# head_board.net
KiCad netlist of a schematic drawn in EAGLE
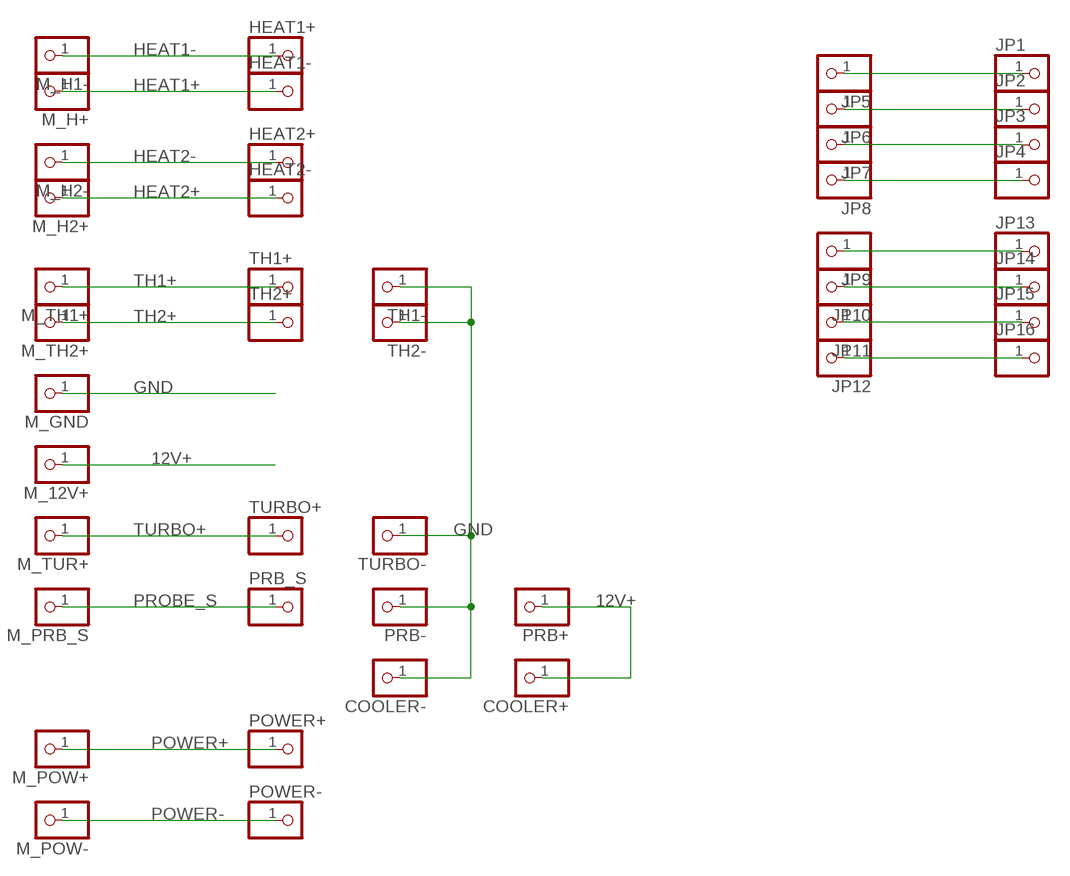
[diagram p0: schematic, sheet 1]

(export (version "E")
  (design (tool "Eeschema 10.0.6"))
  (components
    (comp (ref "COOLER+")
      (value "PINHD-1X1")
      (footprint "eagle-import:1X01")
      (libsource (lib "eagle-import") (part "PINHD-1X1"))
    )
    (comp (ref "COOLER-")
      (value "PINHD-1X1")
      (footprint "eagle-import:1X01")
      (libsource (lib "eagle-import") (part "PINHD-1X1"))
    )
    (comp (ref "HEAT1+")
      (value "PINHD-1X1")
      (footprint "eagle-import:1X01")
      (libsource (lib "eagle-import") (part "PINHD-1X1"))
    )
    (comp (ref "HEAT1-")
      (value "PINHD-1X1")
      (footprint "eagle-import:1X01")
      (libsource (lib "eagle-import") (part "PINHD-1X1"))
    )
    (comp (ref "HEAT2+")
      (value "PINHD-1X1")
      (footprint "eagle-import:1X01")
      (libsource (lib "eagle-import") (part "PINHD-1X1"))
    )
    (comp (ref "HEAT2-")
      (value "PINHD-1X1")
      (footprint "eagle-import:1X01")
      (libsource (lib "eagle-import") (part "PINHD-1X1"))
    )
    (comp (ref "JP1")
      (value "PINHD-1X1")
      (footprint "eagle-import:1X01")
      (libsource (lib "eagle-import") (part "PINHD-1X1"))
    )
    (comp (ref "JP2")
      (value "PINHD-1X1")
      (footprint "eagle-import:1X01")
      (libsource (lib "eagle-import") (part "PINHD-1X1"))
    )
    (comp (ref "JP3")
      (value "PINHD-1X1")
      (footprint "eagle-import:1X01")
      (libsource (lib "eagle-import") (part "PINHD-1X1"))
    )
    (comp (ref "JP4")
      (value "PINHD-1X1")
      (footprint "eagle-import:1X01")
      (libsource (lib "eagle-import") (part "PINHD-1X1"))
    )
    (comp (ref "JP5")
      (value "PINHD-1X1")
      (footprint "eagle-import:1X01")
      (libsource (lib "eagle-import") (part "PINHD-1X1"))
    )
    (comp (ref "JP6")
      (value "PINHD-1X1")
      (footprint "eagle-import:1X01")
      (libsource (lib "eagle-import") (part "PINHD-1X1"))
    )
    (comp (ref "JP7")
      (value "PINHD-1X1")
      (footprint "eagle-import:1X01")
      (libsource (lib "eagle-import") (part "PINHD-1X1"))
    )
    (comp (ref "JP8")
      (value "PINHD-1X1")
      (footprint "eagle-import:1X01")
      (libsource (lib "eagle-import") (part "PINHD-1X1"))
    )
    (comp (ref "JP9")
      (value "PINHD-1X1")
      (footprint "eagle-import:1X01")
      (libsource (lib "eagle-import") (part "PINHD-1X1"))
    )
    (comp (ref "JP10")
      (value "PINHD-1X1")
      (footprint "eagle-import:1X01")
      (libsource (lib "eagle-import") (part "PINHD-1X1"))
    )
    (comp (ref "JP11")
      (value "PINHD-1X1")
      (footprint "eagle-import:1X01")
      (libsource (lib "eagle-import") (part "PINHD-1X1"))
    )
    (comp (ref "JP12")
      (value "PINHD-1X1")
      (footprint "eagle-import:1X01")
      (libsource (lib "eagle-import") (part "PINHD-1X1"))
    )
    (comp (ref "JP13")
      (value "PINHD-1X1")
      (footprint "eagle-import:1X01")
      (libsource (lib "eagle-import") (part "PINHD-1X1"))
    )
    (comp (ref "JP14")
      (value "PINHD-1X1")
      (footprint "eagle-import:1X01")
      (libsource (lib "eagle-import") (part "PINHD-1X1"))
    )
    (comp (ref "JP15")
      (value "PINHD-1X1")
      (footprint "eagle-import:1X01")
      (libsource (lib "eagle-import") (part "PINHD-1X1"))
    )
    (comp (ref "JP16")
      (value "PINHD-1X1")
      (footprint "eagle-import:1X01")
      (libsource (lib "eagle-import") (part "PINHD-1X1"))
    )
    (comp (ref "M_12V+")
      (value "PINHD-1X1")
      (footprint "eagle-import:1X01")
      (libsource (lib "eagle-import") (part "PINHD-1X1"))
    )
    (comp (ref "M_GND")
      (value "PINHD-1X1")
      (footprint "eagle-import:1X01")
      (libsource (lib "eagle-import") (part "PINHD-1X1"))
    )
    (comp (ref "M_H+")
      (value "PINHD-1X1")
      (footprint "eagle-import:1X01")
      (libsource (lib "eagle-import") (part "PINHD-1X1"))
    )
    (comp (ref "M_H1-")
      (value "PINHD-1X1")
      (footprint "eagle-import:1X01")
      (libsource (lib "eagle-import") (part "PINHD-1X1"))
    )
    (comp (ref "M_H2+")
      (value "PINHD-1X1")
      (footprint "eagle-import:1X01")
      (libsource (lib "eagle-import") (part "PINHD-1X1"))
    )
    (comp (ref "M_H2-")
      (value "PINHD-1X1")
      (footprint "eagle-import:1X01")
      (libsource (lib "eagle-import") (part "PINHD-1X1"))
    )
    (comp (ref "M_POW+")
      (value "PINHD-1X1")
      (footprint "eagle-import:1X01")
      (libsource (lib "eagle-import") (part "PINHD-1X1"))
    )
    (comp (ref "M_POW-")
      (value "PINHD-1X1")
      (footprint "eagle-import:1X01")
      (libsource (lib "eagle-import") (part "PINHD-1X1"))
    )
    (comp (ref "M_PRB_S")
      (value "PINHD-1X1")
      (footprint "eagle-import:1X01")
      (libsource (lib "eagle-import") (part "PINHD-1X1"))
    )
    (comp (ref "M_TH1+")
      (value "PINHD-1X1")
      (footprint "eagle-import:1X01")
      (libsource (lib "eagle-import") (part "PINHD-1X1"))
    )
    (comp (ref "M_TH2+")
      (value "PINHD-1X1")
      (footprint "eagle-import:1X01")
      (libsource (lib "eagle-import") (part "PINHD-1X1"))
    )
    (comp (ref "M_TUR+")
      (value "PINHD-1X1")
      (footprint "eagle-import:1X01")
      (libsource (lib "eagle-import") (part "PINHD-1X1"))
    )
    (comp (ref "POWER+")
      (value "PINHD-1X1")
      (footprint "eagle-import:1X01")
      (libsource (lib "eagle-import") (part "PINHD-1X1"))
    )
    (comp (ref "POWER-")
      (value "PINHD-1X1")
      (footprint "eagle-import:1X01")
      (libsource (lib "eagle-import") (part "PINHD-1X1"))
    )
    (comp (ref "PRB+")
      (value "PINHD-1X1")
      (footprint "eagle-import:1X01")
      (libsource (lib "eagle-import") (part "PINHD-1X1"))
    )
    (comp (ref "PRB-")
      (value "PINHD-1X1")
      (footprint "eagle-import:1X01")
      (libsource (lib "eagle-import") (part "PINHD-1X1"))
    )
    (comp (ref "PRB_S")
      (value "PINHD-1X1")
      (footprint "eagle-import:1X01")
      (libsource (lib "eagle-import") (part "PINHD-1X1"))
    )
    (comp (ref "TH1+")
      (value "PINHD-1X1")
      (footprint "eagle-import:1X01")
      (libsource (lib "eagle-import") (part "PINHD-1X1"))
    )
    (comp (ref "TH1-")
      (value "PINHD-1X1")
      (footprint "eagle-import:1X01")
      (libsource (lib "eagle-import") (part "PINHD-1X1"))
    )
    (comp (ref "TH2+")
      (value "PINHD-1X1")
      (footprint "eagle-import:1X01")
      (libsource (lib "eagle-import") (part "PINHD-1X1"))
    )
    (comp (ref "TH2-")
      (value "PINHD-1X1")
      (footprint "eagle-import:1X01")
      (libsource (lib "eagle-import") (part "PINHD-1X1"))
    )
    (comp (ref "TURBO+")
      (value "PINHD-1X1")
      (footprint "eagle-import:1X01")
      (libsource (lib "eagle-import") (part "PINHD-1X1"))
    )
    (comp (ref "TURBO-")
      (value "PINHD-1X1")
      (footprint "eagle-import:1X01")
      (libsource (lib "eagle-import") (part "PINHD-1X1"))
    )
  )
  (nets
    (net (code "1") (name "/12V+") (class "Default")
      (node (ref "COOLER+") (pin "1") (pinfunction "1_1") (pintype "passive"))
      (node (ref "M_12V+") (pin "1") (pinfunction "1_1") (pintype "passive"))
      (node (ref "PRB+") (pin "1") (pinfunction "1_1") (pintype "passive"))
    )
    (net (code "2") (name "/GND") (class "Default")
      (node (ref "COOLER-") (pin "1") (pinfunction "1_1") (pintype "passive"))
      (node (ref "M_GND") (pin "1") (pinfunction "1_1") (pintype "passive"))
      (node (ref "PRB-") (pin "1") (pinfunction "1_1") (pintype "passive"))
      (node (ref "TH1-") (pin "1") (pinfunction "1_1") (pintype "passive"))
      (node (ref "TH2-") (pin "1") (pinfunction "1_1") (pintype "passive"))
      (node (ref "TURBO-") (pin "1") (pinfunction "1_1") (pintype "passive"))
    )
    (net (code "3") (name "/HEAT1+") (class "Default")
      (node (ref "HEAT1-") (pin "1") (pinfunction "1_1") (pintype "passive"))
      (node (ref "M_H+") (pin "1") (pinfunction "1_1") (pintype "passive"))
    )
    (net (code "4") (name "/HEAT1-") (class "Default")
      (node (ref "HEAT1+") (pin "1") (pinfunction "1_1") (pintype "passive"))
      (node (ref "M_H1-") (pin "1") (pinfunction "1_1") (pintype "passive"))
    )
    (net (code "5") (name "/HEAT2+") (class "Default")
      (node (ref "HEAT2-") (pin "1") (pinfunction "1_1") (pintype "passive"))
      (node (ref "M_H2+") (pin "1") (pinfunction "1_1") (pintype "passive"))
    )
    (net (code "6") (name "/HEAT2-") (class "Default")
      (node (ref "HEAT2+") (pin "1") (pinfunction "1_1") (pintype "passive"))
      (node (ref "M_H2-") (pin "1") (pinfunction "1_1") (pintype "passive"))
    )
    (net (code "7") (name "/POWER+") (class "Default")
      (node (ref "M_POW+") (pin "1") (pinfunction "1_1") (pintype "passive"))
      (node (ref "POWER+") (pin "1") (pinfunction "1_1") (pintype "passive"))
    )
    (net (code "8") (name "/POWER-") (class "Default")
      (node (ref "M_POW-") (pin "1") (pinfunction "1_1") (pintype "passive"))
      (node (ref "POWER-") (pin "1") (pinfunction "1_1") (pintype "passive"))
    )
    (net (code "9") (name "/PROBE_S") (class "Default")
      (node (ref "M_PRB_S") (pin "1") (pinfunction "1_1") (pintype "passive"))
      (node (ref "PRB_S") (pin "1") (pinfunction "1_1") (pintype "passive"))
    )
    (net (code "10") (name "/TH1+") (class "Default")
      (node (ref "M_TH1+") (pin "1") (pinfunction "1_1") (pintype "passive"))
      (node (ref "TH1+") (pin "1") (pinfunction "1_1") (pintype "passive"))
    )
    (net (code "11") (name "/TH2+") (class "Default")
      (node (ref "M_TH2+") (pin "1") (pinfunction "1_1") (pintype "passive"))
      (node (ref "TH2+") (pin "1") (pinfunction "1_1") (pintype "passive"))
    )
    (net (code "12") (name "/TURBO+") (class "Default")
      (node (ref "M_TUR+") (pin "1") (pinfunction "1_1") (pintype "passive"))
      (node (ref "TURBO+") (pin "1") (pinfunction "1_1") (pintype "passive"))
    )
    (net (code "13") (name "Net-(JP1-Pad1)") (class "Default")
      (node (ref "JP1") (pin "1") (pinfunction "1_1") (pintype "passive"))
      (node (ref "JP5") (pin "1") (pinfunction "1_1") (pintype "passive"))
    )
    (net (code "14") (name "Net-(JP2-Pad1)") (class "Default")
      (node (ref "JP2") (pin "1") (pinfunction "1_1") (pintype "passive"))
      (node (ref "JP6") (pin "1") (pinfunction "1_1") (pintype "passive"))
    )
    (net (code "15") (name "Net-(JP3-Pad1)") (class "Default")
      (node (ref "JP3") (pin "1") (pinfunction "1_1") (pintype "passive"))
      (node (ref "JP7") (pin "1") (pinfunction "1_1") (pintype "passive"))
    )
    (net (code "16") (name "Net-(JP4-Pad1)") (class "Default")
      (node (ref "JP4") (pin "1") (pinfunction "1_1") (pintype "passive"))
      (node (ref "JP8") (pin "1") (pinfunction "1_1") (pintype "passive"))
    )
    (net (code "17") (name "Net-(JP10-Pad1)") (class "Default")
      (node (ref "JP10") (pin "1") (pinfunction "1_1") (pintype "passive"))
      (node (ref "JP14") (pin "1") (pinfunction "1_1") (pintype "passive"))
    )
    (net (code "18") (name "Net-(JP11-Pad1)") (class "Default")
      (node (ref "JP11") (pin "1") (pinfunction "1_1") (pintype "passive"))
      (node (ref "JP15") (pin "1") (pinfunction "1_1") (pintype "passive"))
    )
    (net (code "19") (name "Net-(JP12-Pad1)") (class "Default")
      (node (ref "JP12") (pin "1") (pinfunction "1_1") (pintype "passive"))
      (node (ref "JP16") (pin "1") (pinfunction "1_1") (pintype "passive"))
    )
    (net (code "20") (name "Net-(JP13-Pad1)") (class "Default")
      (node (ref "JP13") (pin "1") (pinfunction "1_1") (pintype "passive"))
      (node (ref "JP9") (pin "1") (pinfunction "1_1") (pintype "passive"))
    )
  )
)
